# AlienWhoopF0.net
KiCad netlist of a schematic drawn in EAGLE
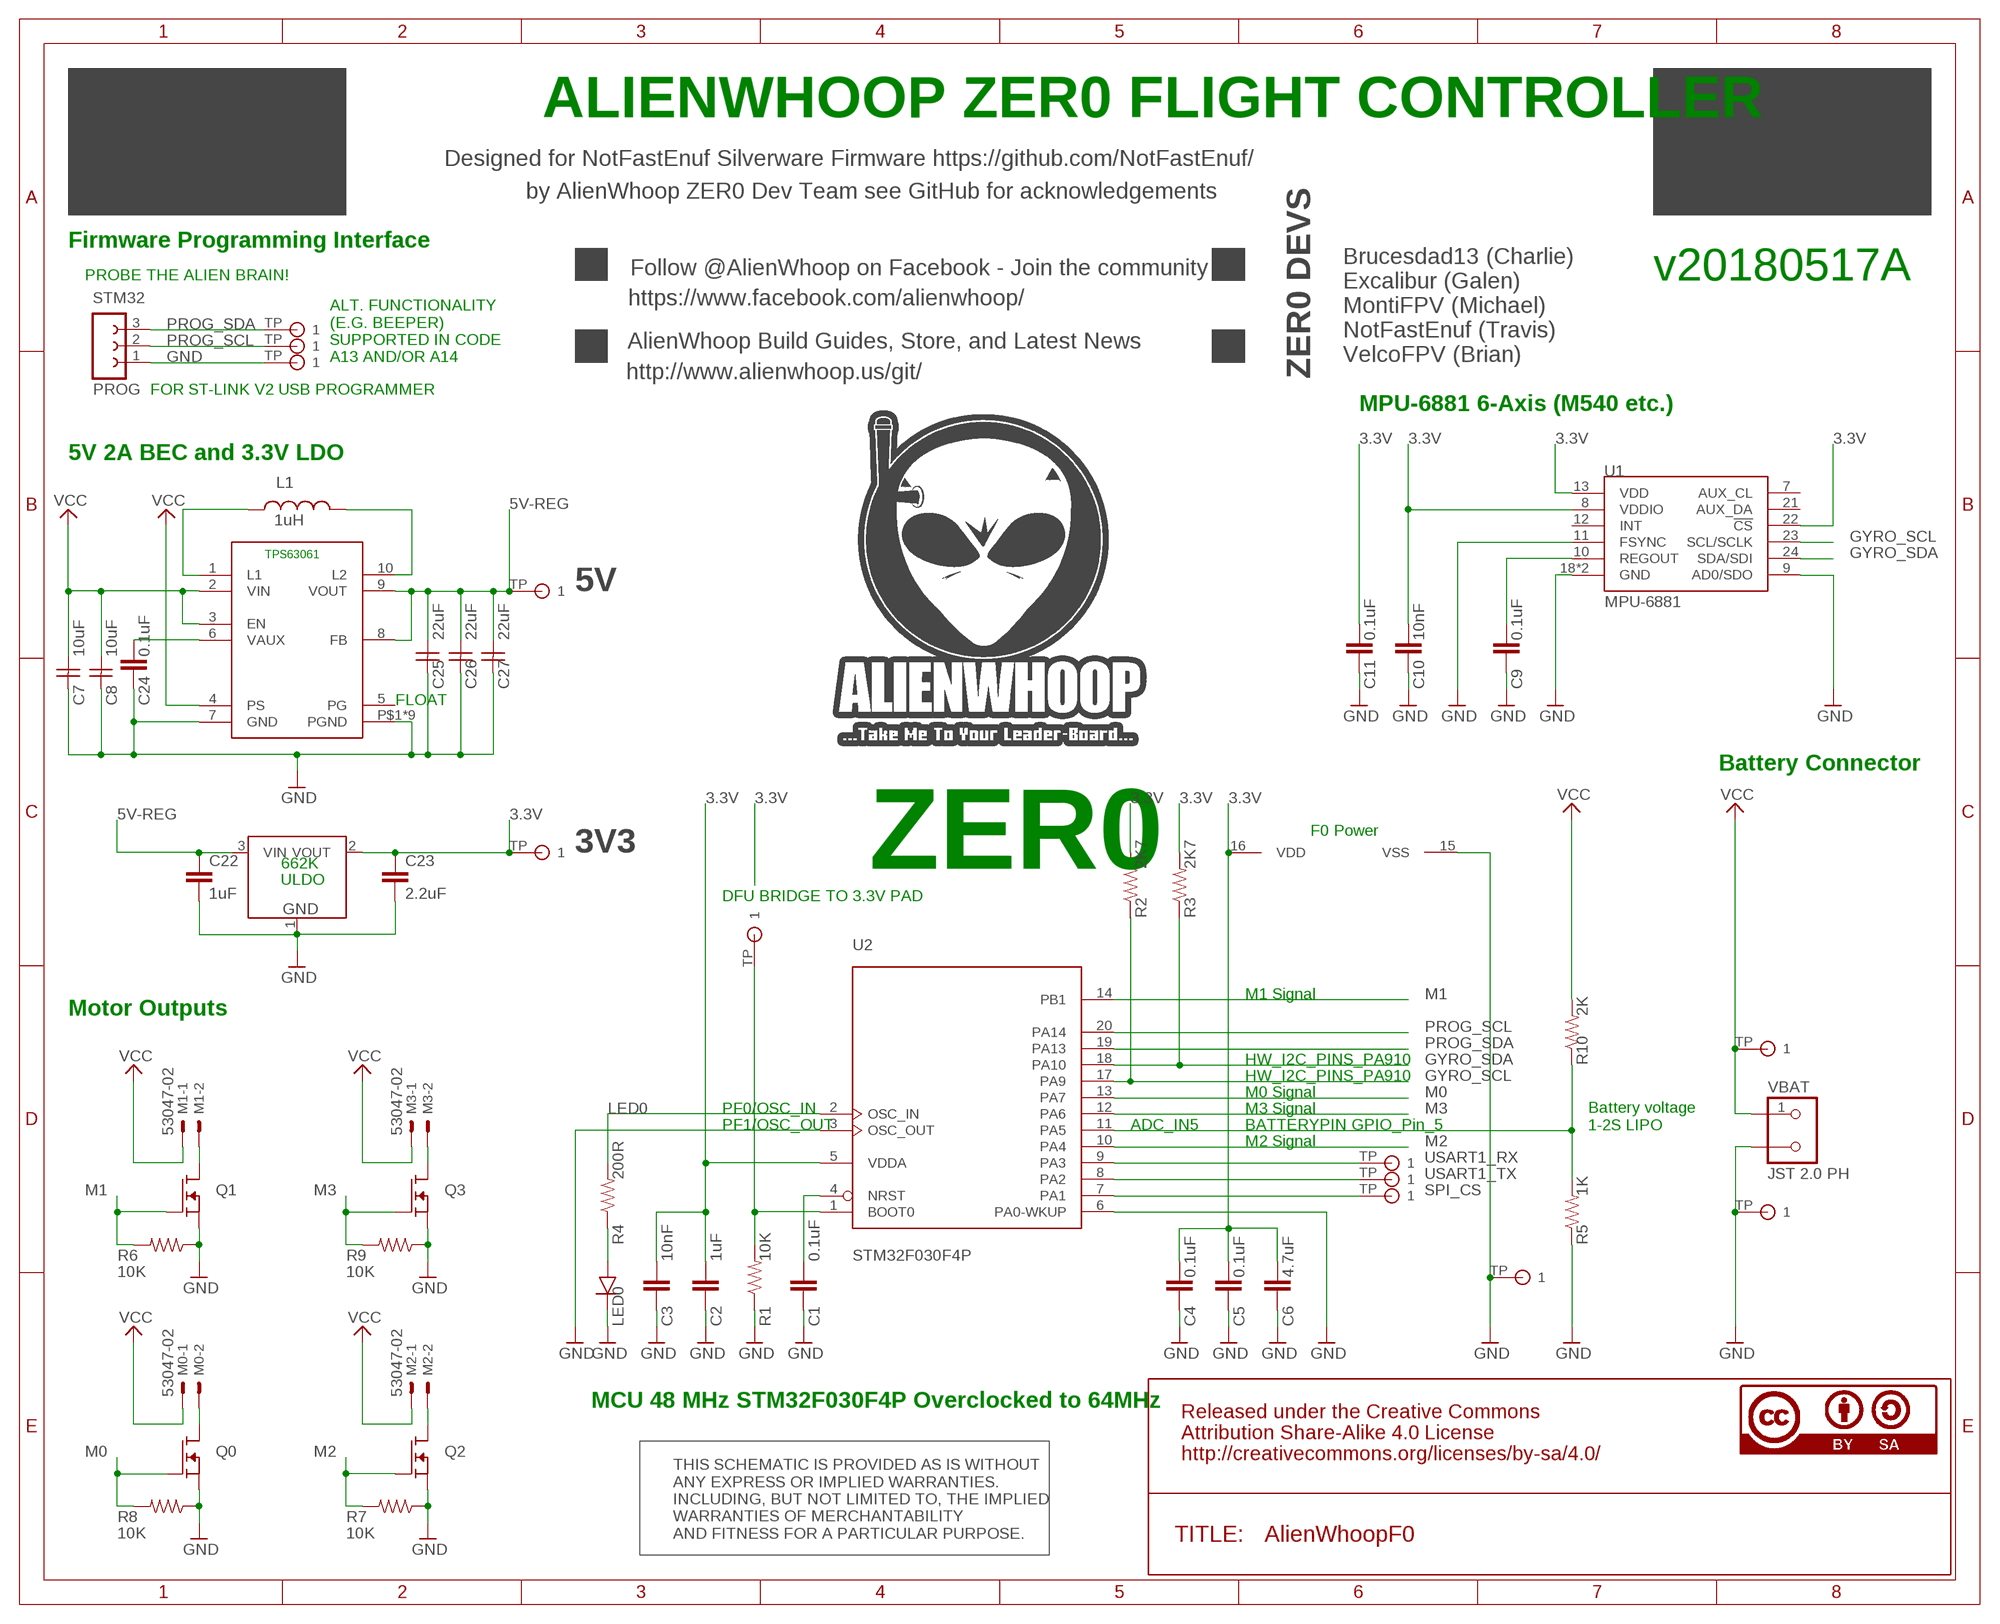
[diagram p0: schematic, sheet 1]

(export (version "E")
  (design (tool "Eeschema 10.0.6"))
  (components
    (comp (ref "+")
      (value "TESTPAD")
      (footprint "eagle-import:TESTPAD")
      (libsource (lib "eagle-import") (part "TESTPAD"))
    )
    (comp (ref "-")
      (value "TESTPAD")
      (footprint "eagle-import:TESTPAD")
      (libsource (lib "eagle-import") (part "TESTPAD"))
    )
    (comp (ref "3.3V2")
      (value "TESTPAD")
      (footprint "eagle-import:TESTPAD")
      (libsource (lib "eagle-import") (part "TESTPAD"))
    )
    (comp (ref "5V2")
      (value "TESTPAD")
      (footprint "eagle-import:TESTPAD")
      (libsource (lib "eagle-import") (part "TESTPAD"))
    )
    (comp (ref "A13")
      (value "TESTPAD")
      (footprint "eagle-import:TESTPAD")
      (libsource (lib "eagle-import") (part "TESTPAD"))
    )
    (comp (ref "A14")
      (value "TESTPAD")
      (footprint "eagle-import:TESTPAD")
      (libsource (lib "eagle-import") (part "TESTPAD"))
    )
    (comp (ref "C1")
      (value "0.1uF")
      (footprint "eagle-import:0402")
      (fields (field (name "PARTNO") "GCM155R71C104KA55D"))
      (libsource (lib "eagle-import") (part "CAP_0402"))
    )
    (comp (ref "C2")
      (value "1uF")
      (footprint "eagle-import:0402")
      (fields (field (name "PARTNO") "GRM155C71A105KE11D"))
      (libsource (lib "eagle-import") (part "CAP_0402"))
    )
    (comp (ref "C3")
      (value "10nF")
      (footprint "eagle-import:0402")
      (fields (field (name "PARTNO") "GCM155R71H103KA55D"))
      (libsource (lib "eagle-import") (part "CAP_0402"))
    )
    (comp (ref "C4")
      (value "0.1uF")
      (footprint "eagle-import:0402")
      (fields (field (name "PARTNO") "GCM155R71C104KA55D"))
      (libsource (lib "eagle-import") (part "CAP_0402"))
    )
    (comp (ref "C5")
      (value "0.1uF")
      (footprint "eagle-import:0402")
      (fields (field (name "PARTNO") "GCM155R71C104KA55D"))
      (libsource (lib "eagle-import") (part "CAP_0402"))
    )
    (comp (ref "C6")
      (value "4.7uF")
      (footprint "eagle-import:0402")
      (fields (field (name "PARTNO") "GRM155R60G475ME47J"))
      (libsource (lib "eagle-import") (part "CAP_0402"))
    )
    (comp (ref "C7")
      (value "10uF")
      (footprint "eagle-import:YUDEN-CAP-0805")
      (fields (field (name "MF") "Taiyo Yuden") (field (name "MPN") "JMK212AB7106KG-T"))
      (libsource (lib "eagle-import") (part "alienflight_298186_CAPACITOR10UF"))
    )
    (comp (ref "C8")
      (value "10uF")
      (footprint "eagle-import:YUDEN-CAP-0805")
      (fields (field (name "MF") "Taiyo Yuden") (field (name "MPN") "JMK212AB7106KG-T"))
      (libsource (lib "eagle-import") (part "alienflight_298186_CAPACITOR10UF"))
    )
    (comp (ref "C9")
      (value "0.1uF")
      (footprint "eagle-import:0402")
      (fields (field (name "PARTNO") "GCM155R71C104KA55D"))
      (libsource (lib "eagle-import") (part "CAP_0402"))
    )
    (comp (ref "C10")
      (value "10nF")
      (footprint "eagle-import:0402")
      (fields (field (name "PARTNO") "GCM155R71H103KA55D"))
      (libsource (lib "eagle-import") (part "CAP_0402"))
    )
    (comp (ref "C11")
      (value "0.1uF")
      (footprint "eagle-import:0402")
      (fields (field (name "PARTNO") "GCM155R71C104KA55D"))
      (libsource (lib "eagle-import") (part "CAP_0402"))
    )
    (comp (ref "C22")
      (value "1uF")
      (footprint "eagle-import:0402")
      (fields (field (name "PARTNO") "GRM155C71A105KE11D"))
      (libsource (lib "eagle-import") (part "CAP_0402"))
    )
    (comp (ref "C23")
      (value "2.2uF")
      (footprint "eagle-import:0402")
      (fields (field (name "PARTNO") "GRM155C70J225KE11D"))
      (libsource (lib "eagle-import") (part "CAP_0402"))
    )
    (comp (ref "C24")
      (value "0.1uF")
      (footprint "eagle-import:0402")
      (fields (field (name "PARTNO") "GCM155R71C104KA55D"))
      (libsource (lib "eagle-import") (part "CAP_0402"))
    )
    (comp (ref "C25")
      (value "22uF")
      (footprint "eagle-import:YUDEN-CAP-0805")
      (fields (field (name "MF") "Taiyo Yuden") (field (name "MPN") "JMK212BJ226MG-T"))
      (libsource (lib "eagle-import") (part "CAPACITOR22UF"))
    )
    (comp (ref "C26")
      (value "22uF")
      (footprint "eagle-import:YUDEN-CAP-0805")
      (fields (field (name "MF") "Taiyo Yuden") (field (name "MPN") "JMK212BJ226MG-T"))
      (libsource (lib "eagle-import") (part "CAPACITOR22UF"))
    )
    (comp (ref "C27")
      (value "22uF")
      (footprint "eagle-import:YUDEN-CAP-0805")
      (fields (field (name "MF") "Taiyo Yuden") (field (name "MPN") "JMK212BJ226MG-T"))
      (libsource (lib "eagle-import") (part "CAPACITOR22UF"))
    )
    (comp (ref "DFU")
      (value "TESTPAD")
      (footprint "eagle-import:TESTPAD")
      (libsource (lib "eagle-import") (part "TESTPAD"))
    )
    (comp (ref "GND23")
      (value "TESTPAD")
      (footprint "eagle-import:TESTPAD")
      (libsource (lib "eagle-import") (part "TESTPAD"))
    )
    (comp (ref "GND@2")
      (value "TESTPAD")
      (footprint "eagle-import:TESTPAD")
      (libsource (lib "eagle-import") (part "TESTPAD"))
    )
    (comp (ref "L1")
      (value "1uH")
      (footprint "eagle-import:DFE201612E-INDUCTOR")
      (fields (field (name "MF") "Murata") (field (name "MPN") "DFE201612E-1R0M=P2"))
      (libsource (lib "eagle-import") (part "DFE201612E-INDUCTOR1UH"))
    )
    (comp (ref "LED0")
      (value "BLUE")
      (footprint "eagle-import:SMD-CHIP-LED-0805")
      (fields (field (name "MF") "Kingbright") (field (name "MPN") "APHCM2012QBC/D-F01"))
      (libsource (lib "eagle-import") (part "SMD-CHIP-LED-0805"))
    )
    (comp (ref "M0")
      (value "53047-02")
      (footprint "eagle-import:53047-02")
      (fields (field (name "MF") "MOLEX") (field (name "MPN") "53047-0210"))
      (libsource (lib "eagle-import") (part "53?-02047"))
    )
    (comp (ref "M1")
      (value "53047-02")
      (footprint "eagle-import:53047-02")
      (fields (field (name "MF") "MOLEX") (field (name "MPN") "53047-0210"))
      (libsource (lib "eagle-import") (part "53?-02047"))
    )
    (comp (ref "M2")
      (value "53047-02")
      (footprint "eagle-import:53047-02")
      (fields (field (name "MF") "MOLEX") (field (name "MPN") "53047-0210"))
      (libsource (lib "eagle-import") (part "53?-02047"))
    )
    (comp (ref "M3")
      (value "53047-02")
      (footprint "eagle-import:53047-02")
      (fields (field (name "MF") "MOLEX") (field (name "MPN") "53047-0210"))
      (libsource (lib "eagle-import") (part "53?-02047"))
    )
    (comp (ref "Q0")
      (value "FDMA410NZ")
      (footprint "eagle-import:MICROFET-2X2")
      (fields (field (name "MF") "Fairchild"))
      (libsource (lib "eagle-import") (part "FDMA410NZ"))
    )
    (comp (ref "Q1")
      (value "FDMA410NZ")
      (footprint "eagle-import:MICROFET-2X2")
      (fields (field (name "MF") "Fairchild"))
      (libsource (lib "eagle-import") (part "FDMA410NZ"))
    )
    (comp (ref "Q2")
      (value "FDMA410NZ")
      (footprint "eagle-import:MICROFET-2X2")
      (fields (field (name "MF") "Fairchild"))
      (libsource (lib "eagle-import") (part "FDMA410NZ"))
    )
    (comp (ref "Q3")
      (value "FDMA410NZ")
      (footprint "eagle-import:MICROFET-2X2")
      (fields (field (name "MF") "Fairchild"))
      (libsource (lib "eagle-import") (part "FDMA410NZ"))
    )
    (comp (ref "Q5")
      (value "3.3V")
      (footprint "eagle-import:SOT-23")
      (fields (field (name "PARTNO") "AP2210N-3.3TRG1"))
      (libsource (lib "eagle-import") (part "AP2210-ULDO3.3V"))
    )
    (comp (ref "R1")
      (value "10K")
      (footprint "eagle-import:0402")
      (fields (field (name "PARTNO") "RC0402FR-0710KL"))
      (libsource (lib "eagle-import") (part "RES_0402"))
    )
    (comp (ref "R2")
      (value "2K7")
      (footprint "eagle-import:0402")
      (fields (field (name "PARTNO") "AC0402JR-072K7L"))
      (libsource (lib "eagle-import") (part "RES_0402"))
    )
    (comp (ref "R3")
      (value "2K7")
      (footprint "eagle-import:0402")
      (fields (field (name "PARTNO") "AC0402JR-072K7L"))
      (libsource (lib "eagle-import") (part "RES_0402"))
    )
    (comp (ref "R4")
      (value "200R")
      (footprint "eagle-import:0402")
      (fields (field (name "PARTNO") "RC0402JR-7D200RL"))
      (libsource (lib "eagle-import") (part "RES_0402"))
    )
    (comp (ref "R5")
      (value "1K")
      (footprint "eagle-import:0402")
      (fields (field (name "PARTNO") "AT0402BRD071KL"))
      (libsource (lib "eagle-import") (part "RES_0402"))
    )
    (comp (ref "R6")
      (value "10K")
      (footprint "eagle-import:0402")
      (fields (field (name "PARTNO") "RC0402FR-0710KL"))
      (libsource (lib "eagle-import") (part "RES_0402"))
    )
    (comp (ref "R7")
      (value "10K")
      (footprint "eagle-import:0402")
      (fields (field (name "PARTNO") "RC0402FR-0710KL"))
      (libsource (lib "eagle-import") (part "RES_0402"))
    )
    (comp (ref "R8")
      (value "10K")
      (footprint "eagle-import:0402")
      (fields (field (name "PARTNO") "RC0402FR-0710KL"))
      (libsource (lib "eagle-import") (part "RES_0402"))
    )
    (comp (ref "R9")
      (value "10K")
      (footprint "eagle-import:0402")
      (fields (field (name "PARTNO") "RC0402FR-0710KL"))
      (libsource (lib "eagle-import") (part "RES_0402"))
    )
    (comp (ref "R10")
      (value "2K")
      (footprint "eagle-import:0402")
      (fields (field (name "PARTNO") "AT0402BRE072KL"))
      (libsource (lib "eagle-import") (part "RES_0402"))
    )
    (comp (ref "SPI_CS")
      (value "TESTPAD")
      (footprint "eagle-import:TESTPAD")
      (libsource (lib "eagle-import") (part "TESTPAD"))
    )
    (comp (ref "STM32")
      (value "PROG")
      (footprint "eagle-import:FE03-1")
      (fields (field (name "BOM") "EXCLUDE") (field (name "DNP") "T"))
      (libsource (lib "eagle-import") (part "FE03-1"))
    )
    (comp (ref "U$13")
      (value "TESTPAD")
      (footprint "eagle-import:TESTPAD")
      (libsource (lib "eagle-import") (part "TESTPAD"))
    )
    (comp (ref "U$14")
      (value "TESTPAD")
      (footprint "eagle-import:TESTPAD")
      (libsource (lib "eagle-import") (part "TESTPAD"))
    )
    (comp (ref "U1")
      (value "MPU-6881")
      (footprint "eagle-import:QFN24_PAD")
      (libsource (lib "eagle-import") (part "MPU-6881"))
    )
    (comp (ref "U2")
      (value "STM32F030F4P")
      (footprint "eagle-import:TSSOP20-I")
      (fields (field (name "PARTNO") "STM32F030F4P6TR"))
      (libsource (lib "eagle-import") (part "STM32F030FP4"))
    )
    (comp (ref "U7")
      (value "TPS63061DSC5V")
      (footprint "eagle-import:TPS6306X")
      (fields (field (name "PARTNO") "TPS63061DSCR"))
      (libsource (lib "eagle-import") (part "TPS63061DSC5V"))
    )
    (comp (ref "VBAT")
      (value "JST 2.0 PH")
      (footprint "eagle-import:S2B-PH-K-S")
      (fields (field (name "MF") "JST") (field (name "MPN") "S2B-PH-K-S"))
      (libsource (lib "eagle-import") (part "JST-PH-BAT"))
    )
  )
  (nets
    (net (code "1") (name "/3.3V") (class "Default")
      (node (ref "3.3V2") (pin "TP") (pinfunction "1_TP") (pintype "bidirectional"))
      (node (ref "C10") (pin "1") (pinfunction "1_1") (pintype "passive"))
      (node (ref "C11") (pin "2") (pinfunction "2_2") (pintype "passive"))
      (node (ref "C2") (pin "1") (pinfunction "1_1") (pintype "passive"))
      (node (ref "C23") (pin "1") (pinfunction "1_1") (pintype "passive"))
      (node (ref "C3") (pin "1") (pinfunction "1_1") (pintype "passive"))
      (node (ref "C4") (pin "1") (pinfunction "1_1") (pintype "passive"))
      (node (ref "C5") (pin "1") (pinfunction "1_1") (pintype "passive"))
      (node (ref "C6") (pin "1") (pinfunction "1_1") (pintype "passive"))
      (node (ref "Q5") (pin "2") (pinfunction "VOUT_2") (pintype "power_in"))
      (node (ref "R2") (pin "2") (pinfunction "2_2") (pintype "passive"))
      (node (ref "R3") (pin "2") (pinfunction "2_2") (pintype "passive"))
      (node (ref "U1") (pin "13") (pinfunction "VDD_13") (pintype "bidirectional"))
      (node (ref "U1") (pin "22") (pinfunction "~{CS}_22") (pintype "bidirectional"))
      (node (ref "U1") (pin "8") (pinfunction "VDDIO_8") (pintype "bidirectional"))
      (node (ref "U2") (pin "16") (pinfunction "VDD_16") (pintype "power_in"))
      (node (ref "U2") (pin "5") (pinfunction "VDDA_5") (pintype "power_in"))
    )
    (net (code "2") (name "/5V-REG") (class "Default")
      (node (ref "5V2") (pin "TP") (pinfunction "1_TP") (pintype "bidirectional"))
      (node (ref "C22") (pin "1") (pinfunction "1_1") (pintype "passive"))
      (node (ref "C25") (pin "1") (pinfunction "1_1") (pintype "passive"))
      (node (ref "C26") (pin "1") (pinfunction "1_1") (pintype "passive"))
      (node (ref "C27") (pin "1") (pinfunction "1_1") (pintype "passive"))
      (node (ref "Q5") (pin "3") (pinfunction "VIN_3") (pintype "power_in"))
      (node (ref "U7") (pin "8") (pinfunction "FB_8") (pintype "bidirectional"))
      (node (ref "U7") (pin "9") (pinfunction "VOUT_9") (pintype "bidirectional"))
    )
    (net (code "3") (name "/GYRO_SCL") (class "Default")
      (node (ref "R2") (pin "1") (pinfunction "1_1") (pintype "passive"))
      (node (ref "U1") (pin "23") (pinfunction "SCL/SCLK_23") (pintype "bidirectional"))
      (node (ref "U2") (pin "17") (pinfunction "PA9_17") (pintype "bidirectional"))
    )
    (net (code "4") (name "/GYRO_SDA") (class "Default")
      (node (ref "R3") (pin "1") (pinfunction "1_1") (pintype "passive"))
      (node (ref "U1") (pin "24") (pinfunction "SDA/SDI_24") (pintype "bidirectional"))
      (node (ref "U2") (pin "18") (pinfunction "PA10_18") (pintype "bidirectional"))
    )
    (net (code "5") (name "/LED0") (class "Default")
      (node (ref "R4") (pin "2") (pinfunction "2_2") (pintype "passive"))
      (node (ref "U2") (pin "2") (pinfunction "OSC_IN_2") (pintype "bidirectional"))
    )
    (net (code "6") (name "/M0") (class "Default")
      (node (ref "Q0") (pin "G") (pinfunction "G_G") (pintype "bidirectional"))
      (node (ref "R8") (pin "2") (pinfunction "2_2") (pintype "passive"))
      (node (ref "U2") (pin "13") (pinfunction "PA7_13") (pintype "bidirectional"))
    )
    (net (code "7") (name "/M1") (class "Default")
      (node (ref "Q1") (pin "G") (pinfunction "G_G") (pintype "bidirectional"))
      (node (ref "R6") (pin "2") (pinfunction "2_2") (pintype "passive"))
      (node (ref "U2") (pin "14") (pinfunction "PB1_14") (pintype "bidirectional"))
    )
    (net (code "8") (name "/M2") (class "Default")
      (node (ref "Q2") (pin "G") (pinfunction "G_G") (pintype "bidirectional"))
      (node (ref "R7") (pin "2") (pinfunction "2_2") (pintype "passive"))
      (node (ref "U2") (pin "10") (pinfunction "PA4_10") (pintype "bidirectional"))
    )
    (net (code "9") (name "/M3") (class "Default")
      (node (ref "Q3") (pin "G") (pinfunction "G_G") (pintype "bidirectional"))
      (node (ref "R9") (pin "2") (pinfunction "2_2") (pintype "passive"))
      (node (ref "U2") (pin "12") (pinfunction "PA6_12") (pintype "bidirectional"))
    )
    (net (code "10") (name "/PROG_SCL") (class "Default")
      (node (ref "A14") (pin "TP") (pinfunction "1_TP") (pintype "bidirectional"))
      (node (ref "STM32") (pin "2") (pinfunction "2_2") (pintype "passive"))
      (node (ref "U2") (pin "20") (pinfunction "PA14_20") (pintype "bidirectional"))
    )
    (net (code "11") (name "/PROG_SDA") (class "Default")
      (node (ref "A13") (pin "TP") (pinfunction "1_TP") (pintype "bidirectional"))
      (node (ref "STM32") (pin "3") (pinfunction "3_3") (pintype "passive"))
      (node (ref "U2") (pin "19") (pinfunction "PA13_19") (pintype "bidirectional"))
    )
    (net (code "12") (name "/SPI_CS") (class "Default")
      (node (ref "SPI_CS") (pin "TP") (pinfunction "1_TP") (pintype "bidirectional"))
      (node (ref "U2") (pin "7") (pinfunction "PA1_7") (pintype "bidirectional"))
    )
    (net (code "13") (name "/USART1_RX") (class "Default")
      (node (ref "U$13") (pin "TP") (pinfunction "1_TP") (pintype "bidirectional"))
      (node (ref "U2") (pin "9") (pinfunction "PA3_9") (pintype "bidirectional"))
    )
    (net (code "14") (name "/USART1_TX") (class "Default")
      (node (ref "U$14") (pin "TP") (pinfunction "1_TP") (pintype "bidirectional"))
      (node (ref "U2") (pin "8") (pinfunction "PA2_8") (pintype "bidirectional"))
    )
    (net (code "15") (name "GND") (class "Default")
      (node (ref "-") (pin "TP") (pinfunction "1_TP") (pintype "bidirectional"))
      (node (ref "C1") (pin "2") (pinfunction "2_2") (pintype "passive"))
      (node (ref "C10") (pin "2") (pinfunction "2_2") (pintype "passive"))
      (node (ref "C11") (pin "1") (pinfunction "1_1") (pintype "passive"))
      (node (ref "C2") (pin "2") (pinfunction "2_2") (pintype "passive"))
      (node (ref "C22") (pin "2") (pinfunction "2_2") (pintype "passive"))
      (node (ref "C23") (pin "2") (pinfunction "2_2") (pintype "passive"))
      (node (ref "C24") (pin "2") (pinfunction "2_2") (pintype "passive"))
      (node (ref "C25") (pin "2") (pinfunction "2_2") (pintype "passive"))
      (node (ref "C26") (pin "2") (pinfunction "2_2") (pintype "passive"))
      (node (ref "C27") (pin "2") (pinfunction "2_2") (pintype "passive"))
      (node (ref "C3") (pin "2") (pinfunction "2_2") (pintype "passive"))
      (node (ref "C4") (pin "2") (pinfunction "2_2") (pintype "passive"))
      (node (ref "C5") (pin "2") (pinfunction "2_2") (pintype "passive"))
      (node (ref "C6") (pin "2") (pinfunction "2_2") (pintype "passive"))
      (node (ref "C7") (pin "2") (pinfunction "2_2") (pintype "passive"))
      (node (ref "C8") (pin "2") (pinfunction "2_2") (pintype "passive"))
      (node (ref "C9") (pin "2") (pinfunction "2_2") (pintype "passive"))
      (node (ref "GND23") (pin "TP") (pinfunction "1_TP") (pintype "bidirectional"))
      (node (ref "GND@2") (pin "TP") (pinfunction "1_TP") (pintype "bidirectional"))
      (node (ref "LED0") (pin "C") (pinfunction "C_C") (pintype "passive"))
      (node (ref "Q0") (pin "S") (pinfunction "S_S") (pintype "bidirectional"))
      (node (ref "Q0") (pin "S1") (pinfunction "S_S1") (pintype "bidirectional"))
      (node (ref "Q1") (pin "S") (pinfunction "S_S") (pintype "bidirectional"))
      (node (ref "Q1") (pin "S1") (pinfunction "S_S1") (pintype "bidirectional"))
      (node (ref "Q2") (pin "S") (pinfunction "S_S") (pintype "bidirectional"))
      (node (ref "Q2") (pin "S1") (pinfunction "S_S1") (pintype "bidirectional"))
      (node (ref "Q3") (pin "S") (pinfunction "S_S") (pintype "bidirectional"))
      (node (ref "Q3") (pin "S1") (pinfunction "S_S1") (pintype "bidirectional"))
      (node (ref "Q5") (pin "1") (pinfunction "GND_1") (pintype "power_in"))
      (node (ref "R1") (pin "1") (pinfunction "1_1") (pintype "passive"))
      (node (ref "R5") (pin "1") (pinfunction "1_1") (pintype "passive"))
      (node (ref "R6") (pin "1") (pinfunction "1_1") (pintype "passive"))
      (node (ref "R7") (pin "1") (pinfunction "1_1") (pintype "passive"))
      (node (ref "R8") (pin "1") (pinfunction "1_1") (pintype "passive"))
      (node (ref "R9") (pin "1") (pinfunction "1_1") (pintype "passive"))
      (node (ref "STM32") (pin "1") (pinfunction "1_1") (pintype "passive"))
      (node (ref "U1") (pin "11") (pinfunction "FSYNC_11") (pintype "bidirectional"))
      (node (ref "U1") (pin "18") (pinfunction "GND_18") (pintype "bidirectional"))
      (node (ref "U1") (pin "20") (pinfunction "GND_20") (pintype "bidirectional"))
      (node (ref "U1") (pin "9") (pinfunction "AD0/SDO_9") (pintype "bidirectional"))
      (node (ref "U2") (pin "15") (pinfunction "VSS_15") (pintype "power_in"))
      (node (ref "U2") (pin "3") (pinfunction "OSC_OUT_3") (pintype "bidirectional"))
      (node (ref "U2") (pin "6") (pinfunction "PA0-WKUP_6") (pintype "bidirectional"))
      (node (ref "U7") (pin "7") (pinfunction "GND_7") (pintype "bidirectional"))
      (node (ref "U7") (pin "P$1") (pinfunction "PGND_P$1") (pintype "bidirectional"))
      (node (ref "U7") (pin "P$17") (pinfunction "PGND_P$17") (pintype "bidirectional"))
      (node (ref "U7") (pin "P$18") (pinfunction "PGND_P$18") (pintype "bidirectional"))
      (node (ref "U7") (pin "P$2") (pinfunction "PGND_P$2") (pintype "bidirectional"))
      (node (ref "U7") (pin "P$21") (pinfunction "PGND_P$21") (pintype "bidirectional"))
      (node (ref "U7") (pin "P$22") (pinfunction "PGND_P$22") (pintype "bidirectional"))
      (node (ref "U7") (pin "P$3") (pinfunction "PGND_P$3") (pintype "bidirectional"))
      (node (ref "U7") (pin "P$4") (pinfunction "PGND_P$4") (pintype "bidirectional"))
      (node (ref "U7") (pin "P$5") (pinfunction "PGND_P$5") (pintype "bidirectional"))
      (node (ref "VBAT") (pin "2") (pinfunction "2_2") (pintype "bidirectional"))
    )
    (net (code "16") (name "Net-(DFU-1)") (class "Default")
      (node (ref "DFU") (pin "TP") (pinfunction "1_TP") (pintype "bidirectional"))
      (node (ref "R1") (pin "2") (pinfunction "2_2") (pintype "passive"))
      (node (ref "U2") (pin "1") (pinfunction "BOOT0_1") (pintype "input"))
    )
    (net (code "17") (name "Net-(L1-1)") (class "Default")
      (node (ref "L1") (pin "P$1") (pinfunction "1_P$1") (pintype "passive"))
      (node (ref "U7") (pin "1") (pinfunction "L1_1") (pintype "bidirectional"))
    )
    (net (code "18") (name "Net-(L1-2)") (class "Default")
      (node (ref "L1") (pin "P$2") (pinfunction "2_P$2") (pintype "passive"))
      (node (ref "U7") (pin "10") (pinfunction "L2_10") (pintype "bidirectional"))
    )
    (net (code "19") (name "Net-(LED0-PadA)") (class "Default")
      (node (ref "LED0") (pin "A") (pinfunction "A_A") (pintype "passive"))
      (node (ref "R4") (pin "1") (pinfunction "1_1") (pintype "passive"))
    )
    (net (code "20") (name "Net-(M0B-S-Pad2)") (class "Default")
      (node (ref "M0") (pin "2") (pinfunction "S_2") (pintype "passive"))
      (node (ref "M0") (pin "2S") (pinfunction "S_2S") (pintype "passive"))
      (node (ref "Q0") (pin "D") (pinfunction "D_D") (pintype "bidirectional"))
      (node (ref "Q0") (pin "D1") (pinfunction "D_D1") (pintype "bidirectional"))
      (node (ref "Q0") (pin "D2") (pinfunction "D_D2") (pintype "bidirectional"))
      (node (ref "Q0") (pin "D3") (pinfunction "D_D3") (pintype "bidirectional"))
      (node (ref "Q0") (pin "D4") (pinfunction "D_D4") (pintype "bidirectional"))
    )
    (net (code "21") (name "Net-(M1B-S-Pad2)") (class "Default")
      (node (ref "M1") (pin "2") (pinfunction "S_2") (pintype "passive"))
      (node (ref "M1") (pin "2S") (pinfunction "S_2S") (pintype "passive"))
      (node (ref "Q1") (pin "D") (pinfunction "D_D") (pintype "bidirectional"))
      (node (ref "Q1") (pin "D1") (pinfunction "D_D1") (pintype "bidirectional"))
      (node (ref "Q1") (pin "D2") (pinfunction "D_D2") (pintype "bidirectional"))
      (node (ref "Q1") (pin "D3") (pinfunction "D_D3") (pintype "bidirectional"))
      (node (ref "Q1") (pin "D4") (pinfunction "D_D4") (pintype "bidirectional"))
    )
    (net (code "22") (name "Net-(M2B-S-Pad2)") (class "Default")
      (node (ref "M2") (pin "2") (pinfunction "S_2") (pintype "passive"))
      (node (ref "M2") (pin "2S") (pinfunction "S_2S") (pintype "passive"))
      (node (ref "Q2") (pin "D") (pinfunction "D_D") (pintype "bidirectional"))
      (node (ref "Q2") (pin "D1") (pinfunction "D_D1") (pintype "bidirectional"))
      (node (ref "Q2") (pin "D2") (pinfunction "D_D2") (pintype "bidirectional"))
      (node (ref "Q2") (pin "D3") (pinfunction "D_D3") (pintype "bidirectional"))
      (node (ref "Q2") (pin "D4") (pinfunction "D_D4") (pintype "bidirectional"))
    )
    (net (code "23") (name "Net-(M3B-S-Pad2)") (class "Default")
      (node (ref "M3") (pin "2") (pinfunction "S_2") (pintype "passive"))
      (node (ref "M3") (pin "2S") (pinfunction "S_2S") (pintype "passive"))
      (node (ref "Q3") (pin "D") (pinfunction "D_D") (pintype "bidirectional"))
      (node (ref "Q3") (pin "D1") (pinfunction "D_D1") (pintype "bidirectional"))
      (node (ref "Q3") (pin "D2") (pinfunction "D_D2") (pintype "bidirectional"))
      (node (ref "Q3") (pin "D3") (pinfunction "D_D3") (pintype "bidirectional"))
      (node (ref "Q3") (pin "D4") (pinfunction "D_D4") (pintype "bidirectional"))
    )
    (net (code "24") (name "Net-(U1-REGOUT)") (class "Default")
      (node (ref "C9") (pin "1") (pinfunction "1_1") (pintype "passive"))
      (node (ref "U1") (pin "10") (pinfunction "REGOUT_10") (pintype "bidirectional"))
    )
    (net (code "25") (name "Net-(U2A-NRST)") (class "Default")
      (node (ref "C1") (pin "1") (pinfunction "1_1") (pintype "passive"))
      (node (ref "U2") (pin "4") (pinfunction "NRST_4") (pintype "bidirectional"))
    )
    (net (code "26") (name "Net-(U2A-PA5)") (class "Default")
      (node (ref "R10") (pin "1") (pinfunction "1_1") (pintype "passive"))
      (node (ref "R5") (pin "2") (pinfunction "2_2") (pintype "passive"))
      (node (ref "U2") (pin "11") (pinfunction "PA5_11") (pintype "bidirectional"))
    )
    (net (code "27") (name "Net-(U7-VAUX)") (class "Default")
      (node (ref "C24") (pin "1") (pinfunction "1_1") (pintype "passive"))
      (node (ref "U7") (pin "6") (pinfunction "VAUX_6") (pintype "bidirectional"))
    )
    (net (code "28") (name "VCC") (class "Default")
      (node (ref "+") (pin "TP") (pinfunction "1_TP") (pintype "bidirectional"))
      (node (ref "C7") (pin "1") (pinfunction "1_1") (pintype "passive"))
      (node (ref "C8") (pin "1") (pinfunction "1_1") (pintype "passive"))
      (node (ref "M0") (pin "1") (pinfunction "S_1") (pintype "passive"))
      (node (ref "M0") (pin "1S") (pinfunction "S_1S") (pintype "passive"))
      (node (ref "M1") (pin "1") (pinfunction "S_1") (pintype "passive"))
      (node (ref "M1") (pin "1S") (pinfunction "S_1S") (pintype "passive"))
      (node (ref "M2") (pin "1") (pinfunction "S_1") (pintype "passive"))
      (node (ref "M2") (pin "1S") (pinfunction "S_1S") (pintype "passive"))
      (node (ref "M3") (pin "1") (pinfunction "S_1") (pintype "passive"))
      (node (ref "M3") (pin "1S") (pinfunction "S_1S") (pintype "passive"))
      (node (ref "R10") (pin "2") (pinfunction "2_2") (pintype "passive"))
      (node (ref "U7") (pin "2") (pinfunction "VIN_2") (pintype "bidirectional"))
      (node (ref "U7") (pin "3") (pinfunction "EN_3") (pintype "bidirectional"))
      (node (ref "U7") (pin "4") (pinfunction "PS_4") (pintype "bidirectional"))
      (node (ref "VBAT") (pin "1") (pinfunction "1_1") (pintype "bidirectional"))
    )
    (net (code "29") (name "unconnected-(U1-AUX_CL-Pad7)") (class "Default")
      (node (ref "U1") (pin "7") (pinfunction "AUX_CL_7") (pintype "bidirectional"))
    )
    (net (code "30") (name "unconnected-(U1-AUX_DA-Pad21)") (class "Default")
      (node (ref "U1") (pin "21") (pinfunction "AUX_DA_21") (pintype "bidirectional"))
    )
    (net (code "31") (name "unconnected-(U1-INT-Pad12)") (class "Default")
      (node (ref "U1") (pin "12") (pinfunction "INT_12") (pintype "bidirectional"))
    )
    (net (code "32") (name "unconnected-(U7-PG-Pad5)") (class "Default")
      (node (ref "U7") (pin "5") (pinfunction "PG_5") (pintype "bidirectional"))
    )
  )
)
